# Sheet1.net
KiCad netlist of a schematic drawn in Altium Designer
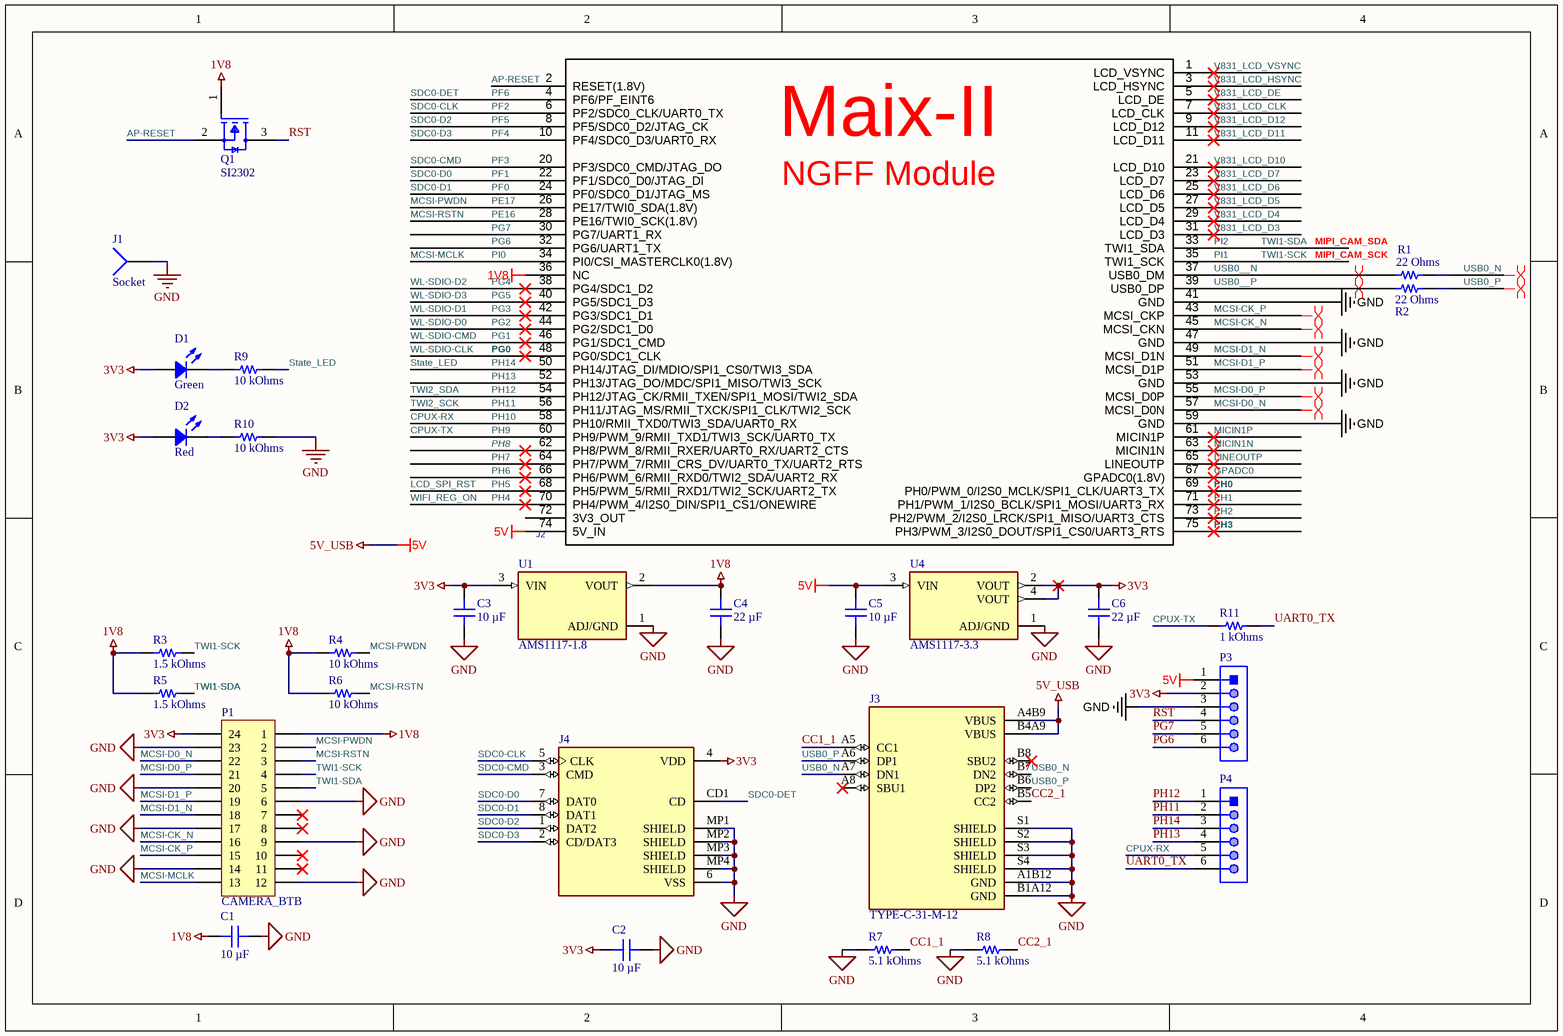
[diagram p0: Sheet1.SchDoc]

(export (version "E")
  (design (tool "Eeschema 10.0.6"))
  (components
    (comp (ref "C1")
      (value "10 µF")
      (footprint "CAP 0402_1005")
      (description "CAP CER 10UF 2.5V X5R 0402")
      (fields
        (field (name "PART NUMBER") "GRM155R60E106ME16D")
        (field (name "MANUFACTURER") "Murata Electronics")
      )
      (libsource (lib "Celestial Altium Library - altium_library") (part "Capacitor"))
    )
    (comp (ref "C2")
      (value "10 µF")
      (footprint "CAP 0402_1005")
      (description "CAP CER 10UF 2.5V X5R 0402")
      (fields
        (field (name "PART NUMBER") "GRM155R60E106ME16D")
        (field (name "MANUFACTURER") "Murata Electronics")
      )
      (libsource (lib "Celestial Altium Library - altium_library") (part "Capacitor"))
    )
    (comp (ref "C3")
      (value "10 µF")
      (footprint "CAP 0402_1005")
      (description "CAP CER 10UF 2.5V X5R 0402")
      (fields
        (field (name "PART NUMBER") "GRM155R60E106ME16D")
        (field (name "MANUFACTURER") "Murata Electronics")
      )
      (libsource (lib "Celestial Altium Library - altium_library") (part "Capacitor"))
    )
    (comp (ref "C4")
      (value "22 µF")
      (footprint "CAP_TAN_A1206")
      (description "CAP CER 10UF 2.5V X5R 0402")
      (fields
        (field (name "PART NUMBER") "GRM155R60E106ME16D")
        (field (name "MANUFACTURER") "Murata Electronics")
      )
      (libsource (lib "Celestial Altium Library - altium_library") (part "Capacitor"))
    )
    (comp (ref "C5")
      (value "10 µF")
      (footprint "CAP 0402_1005")
      (description "CAP CER 10UF 2.5V X5R 0402")
      (fields
        (field (name "PART NUMBER") "GRM155R60E106ME16D")
        (field (name "MANUFACTURER") "Murata Electronics")
      )
      (libsource (lib "Celestial Altium Library - altium_library") (part "Capacitor"))
    )
    (comp (ref "C6")
      (value "22 µF")
      (footprint "CAP_TAN_A1206")
      (description "CAP CER 10UF 2.5V X5R 0402")
      (fields
        (field (name "PART NUMBER") "GRM155R60E106ME16D")
        (field (name "MANUFACTURER") "Murata Electronics")
      )
      (libsource (lib "Celestial Altium Library - altium_library") (part "Capacitor"))
    )
    (comp (ref "D1")
      (value "Green")
      (footprint "LED_0603_GREEN")
      (description "LED GREEN CLEAR 2SMD")
      (fields
        (field (name "PART NUMBER") "EAST10052GA0")
        (field (name "MANUFACTURER") "Everlight Electronics Co Ltd")
      )
      (libsource (lib "Celestial Altium Library - altium_library") (part "LED"))
    )
    (comp (ref "D2")
      (value "Red")
      (footprint "LED_0603_RED")
      (description "0402 LED RED, CLEAR LENS, 330MCD")
      (fields (field (name "PART NUMBER") "QBLP595-R-2897") (field (name "MANUFACTURER") "QT Brightek (QTB)"))
      (libsource (lib "Celestial Altium Library - altium_library") (part "LED"))
    )
    (comp (ref "J1")
      (value "Socket")
      (footprint "M.2 SMT-FEMALE - FULL")
      (fields (field (name "PUBLISHER") "Altium Limited"))
      (libsource (lib "Miscellaneous Connectors") (part "Socket"))
    )
    (comp (ref "J2")
      (value "NGFF-67P_B-KEY座子 4.2H高")
      (footprint "M2-67P0R50_B_FEMALE")
      (libsource (lib "V831_Dock_3060") (part "NGFF-67P_B-MALE"))
    )
    (comp (ref "J3")
      (value "TYPE-C-31-M-12")
      (footprint "HRO_TYPE-C-31-M-12")
      (description "USB Connectors 24 Receptacle 1 8.94*7.3mm RoHS")
      (fields (field (name "MF") "{'manufacturer': u'HRO Electronics Co., Ltd.'}"))
      (libsource (lib "SnapEDA_Library") (part "TYPE-C-31-M-12"))
    )
    (comp (ref "J4")
      (value "TF-01A")
      (footprint "TF-01A")
      (fields (field (name "MF") "{'manufacturer': u'HRO Electronics Co., Ltd.'}"))
      (libsource (lib "SnapEDA_Library") (part "TF-01A"))
    )
    (comp (ref "P1")
      (value "CAMERA_BTB")
      (footprint "F_24PIN")
      (description "Header, 12-Pin, Dual row")
      (fields (field (name "PUBLISHER") "Altium Limited"))
      (libsource (lib "maix_2") (part "Header 12X2A"))
    )
    (comp (ref "P3")
      (value "61300611121")
      (footprint "61300611121")
      (description "THT Vertical Pin Header WR-PHD, Pitch 2.54 mm, Single Row, 6 pins")
      (fields (field (name "MANUFACTURER") "Wurth Elektronik") (field (name "PUBLISHER") "WurthElektronik"))
      (libsource (lib "Altium Content Vault") (part "WE-CN-1P-M-R6"))
    )
    (comp (ref "P4")
      (value "61300611121")
      (footprint "61300611121")
      (description "THT Vertical Pin Header WR-PHD, Pitch 2.54 mm, Single Row, 6 pins")
      (fields (field (name "MANUFACTURER") "Wurth Elektronik") (field (name "PUBLISHER") "WurthElektronik"))
      (libsource (lib "Altium Content Vault") (part "WE-CN-1P-M-R6"))
    )
    (comp (ref "Q1")
      (value "SI2302")
      (footprint "FP-S-03946-IPC_B")
      (description "MOSFET N-CH 20V 2.9A SOT23-3")
      (libsource (lib "Altium Content Vault") (part "0a9ea7c96deaaede766a5b531c28de0"))
    )
    (comp (ref "R1")
      (value "22 Ohms")
      (footprint "RES 0402_1005")
      (description "RES 22 OHM 1% 1/8W 0402")
      (fields (field (name "PART NUMBER") "SR0402FR-7W22RL") (field (name "MANUFACTURER") "Yageo"))
      (libsource (lib "Celestial Altium Library - altium_library") (part "Resistor"))
    )
    (comp (ref "R2")
      (value "22 Ohms")
      (footprint "RES 0402_1005")
      (description "RES 22 OHM 1% 1/8W 0402")
      (fields (field (name "PART NUMBER") "SR0402FR-7W22RL") (field (name "MANUFACTURER") "Yageo"))
      (libsource (lib "Celestial Altium Library - altium_library") (part "Resistor"))
    )
    (comp (ref "R3")
      (value "1.5 kOhms")
      (footprint "RES 0402_1005")
      (description "PTN0402 10PPM 1.5K 0.1% S T1 E1")
      (fields
        (field (name "PART NUMBER") "PTN0402Y1501BST1")
        (field (name "MANUFACTURER") "Vishay Dale Thin Film")
      )
      (libsource (lib "Celestial Altium Library - altium_library") (part "Resistor"))
    )
    (comp (ref "R4")
      (value "10 kOhms")
      (footprint "RES 0402_1005")
      (description "P2TC0402 2PPM/C 10K 0,01% N TA")
      (fields
        (field (name "PART NUMBER") "P2TC0402D1002LNTA")
        (field (name "MANUFACTURER") "Vishay Sfernice")
      )
      (libsource (lib "Celestial Altium Library - altium_library") (part "Resistor"))
    )
    (comp (ref "R5")
      (value "1.5 kOhms")
      (footprint "RES 0402_1005")
      (description "PTN0402 10PPM 1.5K 0.1% S T1 E1")
      (fields
        (field (name "PART NUMBER") "PTN0402Y1501BST1")
        (field (name "MANUFACTURER") "Vishay Dale Thin Film")
      )
      (libsource (lib "Celestial Altium Library - altium_library") (part "Resistor"))
    )
    (comp (ref "R6")
      (value "10 kOhms")
      (footprint "RES 0402_1005")
      (description "P2TC0402 2PPM/C 10K 0,01% N TA")
      (fields
        (field (name "PART NUMBER") "P2TC0402D1002LNTA")
        (field (name "MANUFACTURER") "Vishay Sfernice")
      )
      (libsource (lib "Celestial Altium Library - altium_library") (part "Resistor"))
    )
    (comp (ref "R7")
      (value "5.1 kOhms")
      (footprint "RES 0402_1005")
      (description "RES 5.1K OHM 0.1% 1/16W 0402")
      (fields
        (field (name "PART NUMBER") "RN73R1ETTP5101B25")
        (field (name "MANUFACTURER") "KOA Speer Electronics, Inc.")
      )
      (libsource (lib "Celestial Altium Library - altium_library") (part "Resistor"))
    )
    (comp (ref "R8")
      (value "5.1 kOhms")
      (footprint "RES 0402_1005")
      (description "RES 5.1K OHM 0.1% 1/16W 0402")
      (fields
        (field (name "PART NUMBER") "RN73R1ETTP5101B25")
        (field (name "MANUFACTURER") "KOA Speer Electronics, Inc.")
      )
      (libsource (lib "Celestial Altium Library - altium_library") (part "Resistor"))
    )
    (comp (ref "R9")
      (value "10 kOhms")
      (footprint "RES 0402_1005")
      (description "RES 10K OHM 0.1% 1/10W 0402")
      (fields
        (field (name "PART NUMBER") "RP73PF1E10KBTD")
        (field (name "MANUFACTURER") "TE Connectivity Passive Product")
      )
      (libsource (lib "Celestial Altium Library - altium_library") (part "Resistor"))
    )
    (comp (ref "R10")
      (value "10 kOhms")
      (footprint "RES 0402_1005")
      (description "RES 10K OHM 0.1% 1/10W 0402")
      (fields
        (field (name "PART NUMBER") "RP73PF1E10KBTD")
        (field (name "MANUFACTURER") "TE Connectivity Passive Product")
      )
      (libsource (lib "Celestial Altium Library - altium_library") (part "Resistor"))
    )
    (comp (ref "R11")
      (value "1 kOhms")
      (footprint "RES 0402_1005")
      (description "RES 1K OHM 0.01% 1/16W 0402")
      (fields
        (field (name "PART NUMBER") "RNCF0402TKY1K00")
        (field (name "MANUFACTURER") "Stackpole Electronics Inc")
      )
      (libsource (lib "Celestial Altium Library - altium_library") (part "Resistor"))
    )
    (comp (ref "U1")
      (value "AMS1117-1.8")
      (footprint "SOT89-3")
      (description "Sot223/Pkg 1-Amp 5-Volt Low Drop Out Voltage Regulatator")
      (fields
        (field (name "MP") "AMS1117")
        (field (name "MF") "{'manufacturer': u'Advanced Monolithic Systems'}")
      )
      (libsource (lib "maix_2") (part "AMS1117"))
    )
    (comp (ref "U4")
      (value "AMS1117-3.3")
      (footprint "SOT229P700X180-4N")
      (description "Sot223/Pkg 1-Amp 5-Volt Low Drop Out Voltage Regulatator")
      (fields
        (field (name "MP") "AMS1117")
        (field (name "MF") "{'manufacturer': u'Advanced Monolithic Systems'}")
      )
      (libsource (lib "") (part "AMS1117_1"))
    )
  )
  (nets
    (net (code "1") (name "/AP-RESET") (class "Default")
      (node (ref "J2") (pin "2") (pinfunction "RESET(1.8V)_2") (pintype "passive"))
      (node (ref "Q1") (pin "2") (pinfunction "S_2") (pintype "passive"))
    )
    (net (code "2") (name "/CC1_1") (class "Default")
      (node (ref "J3") (pin "A5") (pinfunction "CC1_A5") (pintype "bidirectional"))
      (node (ref "R7") (pin "2") (pinfunction "2_2") (pintype "passive"))
    )
    (net (code "3") (name "/CC2_1") (class "Default")
      (node (ref "J3") (pin "B5") (pinfunction "CC2_B5") (pintype "bidirectional"))
      (node (ref "R8") (pin "2") (pinfunction "2_2") (pintype "passive"))
    )
    (net (code "4") (name "/CPUX-RX") (class "Default")
      (node (ref "J2") (pin "58") (pinfunction "PH10/RMII_TXD0/TWI3_SDA/UART0_RX_58") (pintype "passive"))
      (node (ref "P4") (pin "5") (pinfunction "5_5") (pintype "passive"))
    )
    (net (code "5") (name "/CPUX-TX") (class "Default")
      (node (ref "J2") (pin "60") (pinfunction "PH9/PWM_9/RMII_TXD1/TWI3_SCK/UART0_TX_60") (pintype "passive"))
      (node (ref "R11") (pin "1") (pinfunction "1_1") (pintype "passive"))
    )
    (net (code "6") (name "/GPADC0") (class "Default")
      (node (ref "J2") (pin "67") (pinfunction "GPADC0(1.8V)_67") (pintype "passive+no_connect"))
    )
    (net (code "7") (name "/LCD_SPI_RST") (class "Default")
      (node (ref "J2") (pin "68") (pinfunction "PH5/PWM_5/RMII_RXD1/TWI2_SCK/UART2_TX_68") (pintype "passive+no_connect"))
    )
    (net (code "8") (name "/LINEOUTP") (class "Default")
      (node (ref "J2") (pin "65") (pinfunction "LINEOUTP_65") (pintype "passive+no_connect"))
    )
    (net (code "9") (name "/MCSI-CK_N") (class "Default")
      (node (ref "J2") (pin "45") (pinfunction "MCSI_CKN_45") (pintype "passive"))
      (node (ref "P1") (pin "16") (pinfunction "16_16") (pintype "passive"))
    )
    (net (code "10") (name "/MCSI-CK_P") (class "Default")
      (node (ref "J2") (pin "43") (pinfunction "MCSI_CKP_43") (pintype "passive"))
      (node (ref "P1") (pin "15") (pinfunction "15_15") (pintype "passive"))
    )
    (net (code "11") (name "/MCSI-D0_N") (class "Default")
      (node (ref "J2") (pin "57") (pinfunction "MCSI_D0N_57") (pintype "passive"))
      (node (ref "P1") (pin "22") (pinfunction "22_22") (pintype "passive"))
    )
    (net (code "12") (name "/MCSI-D0_P") (class "Default")
      (node (ref "J2") (pin "55") (pinfunction "MCSI_D0P_55") (pintype "passive"))
      (node (ref "P1") (pin "21") (pinfunction "21_21") (pintype "passive"))
    )
    (net (code "13") (name "/MCSI-D1_N") (class "Default")
      (node (ref "J2") (pin "49") (pinfunction "MCSI_D1N_49") (pintype "passive"))
      (node (ref "P1") (pin "18") (pinfunction "18_18") (pintype "passive"))
    )
    (net (code "14") (name "/MCSI-D1_P") (class "Default")
      (node (ref "J2") (pin "51") (pinfunction "MCSI_D1P_51") (pintype "passive"))
      (node (ref "P1") (pin "19") (pinfunction "19_19") (pintype "passive"))
    )
    (net (code "15") (name "/MCSI-MCLK") (class "Default")
      (node (ref "J2") (pin "34") (pinfunction "PI0/CSI_MASTERCLK0(1.8V)_34") (pintype "passive"))
      (node (ref "P1") (pin "13") (pinfunction "13_13") (pintype "passive"))
    )
    (net (code "16") (name "/MCSI-PWDN") (class "Default")
      (node (ref "J2") (pin "26") (pinfunction "PE17/TWI0_SDA(1.8V)_26") (pintype "passive"))
      (node (ref "P1") (pin "2") (pinfunction "2_2") (pintype "passive"))
      (node (ref "R4") (pin "2") (pinfunction "2_2") (pintype "passive"))
    )
    (net (code "17") (name "/MCSI-RSTN") (class "Default")
      (node (ref "J2") (pin "28") (pinfunction "PE16/TWI0_SCK(1.8V)_28") (pintype "passive"))
      (node (ref "P1") (pin "3") (pinfunction "3_3") (pintype "passive"))
      (node (ref "R6") (pin "2") (pinfunction "2_2") (pintype "passive"))
    )
    (net (code "18") (name "/MICIN1N") (class "Default")
      (node (ref "J2") (pin "63") (pinfunction "MICIN1N_63") (pintype "passive+no_connect"))
    )
    (net (code "19") (name "/MICIN1P") (class "Default")
      (node (ref "J2") (pin "61") (pinfunction "MICIN1P_61") (pintype "passive+no_connect"))
    )
    (net (code "20") (name "/PF0") (class "Default")
      (node (ref "J2") (pin "24") (pinfunction "PF0/SDC0_D1/JTAG_MS_24") (pintype "passive"))
      (node (ref "J4") (pin "8") (pinfunction "DAT1_8") (pintype "bidirectional"))
    )
    (net (code "21") (name "/PF1") (class "Default")
      (node (ref "J2") (pin "22") (pinfunction "PF1/SDC0_D0/JTAG_DI_22") (pintype "passive"))
      (node (ref "J4") (pin "7") (pinfunction "DAT0_7") (pintype "bidirectional"))
    )
    (net (code "22") (name "/PF2") (class "Default")
      (node (ref "J2") (pin "6") (pinfunction "PF2/SDC0_CLK/UART0_TX_6") (pintype "passive"))
      (node (ref "J4") (pin "5") (pinfunction "CLK_5") (pintype "bidirectional"))
    )
    (net (code "23") (name "/PF3") (class "Default")
      (node (ref "J2") (pin "20") (pinfunction "PF3/SDC0_CMD/JTAG_DO_20") (pintype "passive"))
      (node (ref "J4") (pin "3") (pinfunction "CMD_3") (pintype "bidirectional"))
    )
    (net (code "24") (name "/PF4") (class "Default")
      (node (ref "J2") (pin "10") (pinfunction "PF4/SDC0_D3/UART0_RX_10") (pintype "passive"))
      (node (ref "J4") (pin "2") (pinfunction "CD/DAT3_2") (pintype "bidirectional"))
    )
    (net (code "25") (name "/PF5") (class "Default")
      (node (ref "J2") (pin "8") (pinfunction "PF5/SDC0_D2/JTAG_CK_8") (pintype "passive"))
      (node (ref "J4") (pin "1") (pinfunction "DAT2_1") (pintype "bidirectional"))
    )
    (net (code "26") (name "/PF6") (class "Default")
      (node (ref "J2") (pin "4") (pinfunction "PF6/PF_EINT6_4") (pintype "passive"))
      (node (ref "J4") (pin "CD1") (pinfunction "CD_CD1") (pintype "passive"))
    )
    (net (code "27") (name "/PG0") (class "Default")
      (node (ref "J2") (pin "48") (pinfunction "PG0/SDC1_CLK_48") (pintype "passive+no_connect"))
    )
    (net (code "28") (name "/PG1") (class "Default")
      (node (ref "J2") (pin "46") (pinfunction "PG1/SDC1_CMD_46") (pintype "passive+no_connect"))
    )
    (net (code "29") (name "/PG2") (class "Default")
      (node (ref "J2") (pin "44") (pinfunction "PG2/SDC1_D0_44") (pintype "passive+no_connect"))
    )
    (net (code "30") (name "/PG3") (class "Default")
      (node (ref "J2") (pin "42") (pinfunction "PG3/SDC1_D1_42") (pintype "passive+no_connect"))
    )
    (net (code "31") (name "/PG4") (class "Default")
      (node (ref "J2") (pin "38") (pinfunction "PG4/SDC1_D2_38") (pintype "passive+no_connect"))
    )
    (net (code "32") (name "/PG5") (class "Default")
      (node (ref "J2") (pin "40") (pinfunction "PG5/SDC1_D3_40") (pintype "passive+no_connect"))
    )
    (net (code "33") (name "/PG6") (class "Default")
      (node (ref "J2") (pin "32") (pinfunction "PG6/UART1_TX_32") (pintype "passive"))
      (node (ref "P3") (pin "6") (pinfunction "6_6") (pintype "passive"))
    )
    (net (code "34") (name "/PG7") (class "Default")
      (node (ref "J2") (pin "30") (pinfunction "PG7/UART1_RX_30") (pintype "passive"))
      (node (ref "P3") (pin "5") (pinfunction "5_5") (pintype "passive"))
    )
    (net (code "35") (name "/PH0") (class "Default")
      (node (ref "J2") (pin "69") (pinfunction "PH0/PWM_0/I2S0_MCLK/SPI1_CLK/UART3_TX_69") (pintype "passive+no_connect"))
    )
    (net (code "36") (name "/PH1") (class "Default")
      (node (ref "J2") (pin "71") (pinfunction "PH1/PWM_1/I2S0_BCLK/SPI1_MOSI/UART3_RX_71") (pintype "passive+no_connect"))
    )
    (net (code "37") (name "/PH2") (class "Default")
      (node (ref "J2") (pin "73") (pinfunction "PH2/PWM_2/I2S0_LRCK/SPI1_MISO/UART3_CTS_73") (pintype "passive+no_connect"))
    )
    (net (code "38") (name "/PH3") (class "Default")
      (node (ref "J2") (pin "75") (pinfunction "PH3/PWM_3/I2S0_DOUT/SPI1_CS0/UART3_RTS_75") (pintype "passive+no_connect"))
    )
    (net (code "39") (name "/PH4") (class "Default")
      (node (ref "J2") (pin "70") (pinfunction "PH4/PWM_4/I2S0_DIN/SPI1_CS1/ONEWIRE_70") (pintype "passive+no_connect"))
    )
    (net (code "40") (name "/PH6") (class "Default")
      (node (ref "J2") (pin "66") (pinfunction "PH6/PWM_6/RMII_RXD0/TWI2_SDA/UART2_RX_66") (pintype "passive+no_connect"))
    )
    (net (code "41") (name "/PH7") (class "Default")
      (node (ref "J2") (pin "64") (pinfunction "PH7/PWM_7/RMII_CRS_DV/UART0_TX/UART2_RTS_64") (pintype "passive+no_connect"))
    )
    (net (code "42") (name "/PH8") (class "Default")
      (node (ref "J2") (pin "62") (pinfunction "PH8/PWM_8/RMII_RXER/UART0_RX/UART2_CTS_62") (pintype "passive+no_connect"))
    )
    (net (code "43") (name "/PH11") (class "Default")
      (node (ref "J2") (pin "56") (pinfunction "PH11/JTAG_MS/RMII_TXCK/SPI1_CLK/TWI2_SCK_56") (pintype "passive"))
      (node (ref "P4") (pin "2") (pinfunction "2_2") (pintype "passive"))
    )
    (net (code "44") (name "/PH12") (class "Default")
      (node (ref "J2") (pin "54") (pinfunction "PH12/JTAG_CK/RMII_TXEN/SPI1_MOSI/TWI2_SDA_54") (pintype "passive"))
      (node (ref "P4") (pin "1") (pinfunction "1_1") (pintype "passive"))
    )
    (net (code "45") (name "/PH13") (class "Default")
      (node (ref "J2") (pin "52") (pinfunction "PH13/JTAG_DO/MDC/SPI1_MISO/TWI3_SCK_52") (pintype "passive"))
      (node (ref "P4") (pin "4") (pinfunction "4_4") (pintype "passive"))
    )
    (net (code "46") (name "/PH14") (class "Default")
      (node (ref "J2") (pin "50") (pinfunction "PH14/JTAG_DI/MDIO/SPI1_CS0/TWI3_SDA_50") (pintype "passive"))
      (node (ref "P4") (pin "3") (pinfunction "3_3") (pintype "passive"))
      (node (ref "R9") (pin "2") (pinfunction "2_2") (pintype "passive"))
    )
    (net (code "47") (name "/PI1") (class "Default")
      (node (ref "J2") (pin "35") (pinfunction "TWI1_SCK_35") (pintype "passive"))
      (node (ref "P1") (pin "4") (pinfunction "4_4") (pintype "passive"))
      (node (ref "R3") (pin "2") (pinfunction "2_2") (pintype "passive"))
    )
    (net (code "48") (name "/PI2") (class "Default")
      (node (ref "J2") (pin "33") (pinfunction "TWI1_SDA_33") (pintype "passive"))
      (node (ref "P1") (pin "5") (pinfunction "5_5") (pintype "passive"))
      (node (ref "R5") (pin "2") (pinfunction "2_2") (pintype "passive"))
    )
    (net (code "49") (name "/RST") (class "Default")
      (node (ref "P3") (pin "4") (pinfunction "4_4") (pintype "passive"))
      (node (ref "Q1") (pin "3") (pinfunction "D_3") (pintype "passive"))
    )
    (net (code "50") (name "/UART0_TX") (class "Default")
      (node (ref "P4") (pin "6") (pinfunction "6_6") (pintype "passive"))
      (node (ref "R11") (pin "2") (pinfunction "2_2") (pintype "passive"))
    )
    (net (code "51") (name "/USB0_N") (class "Default")
      (node (ref "J3") (pin "A7") (pinfunction "DN1_A7") (pintype "bidirectional"))
      (node (ref "J3") (pin "B7") (pinfunction "DN2_B7") (pintype "bidirectional"))
      (node (ref "R1") (pin "2") (pinfunction "2_2") (pintype "passive"))
    )
    (net (code "52") (name "/USB0_P") (class "Default")
      (node (ref "J3") (pin "A6") (pinfunction "DP1_A6") (pintype "bidirectional"))
      (node (ref "J3") (pin "B6") (pinfunction "DP2_B6") (pintype "bidirectional"))
      (node (ref "R2") (pin "2") (pinfunction "2_2") (pintype "passive"))
    )
    (net (code "53") (name "/USB0__N") (class "Default")
      (node (ref "J2") (pin "37") (pinfunction "USB0_DM_37") (pintype "passive"))
      (node (ref "R1") (pin "1") (pinfunction "1_1") (pintype "passive"))
    )
    (net (code "54") (name "/USB0__P") (class "Default")
      (node (ref "J2") (pin "39") (pinfunction "USB0_DP_39") (pintype "passive"))
      (node (ref "R2") (pin "1") (pinfunction "1_1") (pintype "passive"))
    )
    (net (code "55") (name "/V831_LCD_CLK") (class "Default")
      (node (ref "J2") (pin "7") (pinfunction "LCD_CLK_7") (pintype "passive+no_connect"))
    )
    (net (code "56") (name "/V831_LCD_D3") (class "Default")
      (node (ref "J2") (pin "31") (pinfunction "LCD_D3_31") (pintype "passive+no_connect"))
    )
    (net (code "57") (name "/V831_LCD_D4") (class "Default")
      (node (ref "J2") (pin "29") (pinfunction "LCD_D4_29") (pintype "passive+no_connect"))
    )
    (net (code "58") (name "/V831_LCD_D5") (class "Default")
      (node (ref "J2") (pin "27") (pinfunction "LCD_D5_27") (pintype "passive+no_connect"))
    )
    (net (code "59") (name "/V831_LCD_D6") (class "Default")
      (node (ref "J2") (pin "25") (pinfunction "LCD_D6_25") (pintype "passive+no_connect"))
    )
    (net (code "60") (name "/V831_LCD_D7") (class "Default")
      (node (ref "J2") (pin "23") (pinfunction "LCD_D7_23") (pintype "passive+no_connect"))
    )
    (net (code "61") (name "/V831_LCD_D10") (class "Default")
      (node (ref "J2") (pin "21") (pinfunction "LCD_D10_21") (pintype "passive+no_connect"))
    )
    (net (code "62") (name "/V831_LCD_D11") (class "Default")
      (node (ref "J2") (pin "11") (pinfunction "LCD_D11_11") (pintype "passive+no_connect"))
    )
    (net (code "63") (name "/V831_LCD_D12") (class "Default")
      (node (ref "J2") (pin "9") (pinfunction "LCD_D12_9") (pintype "passive+no_connect"))
    )
    (net (code "64") (name "/V831_LCD_DE") (class "Default")
      (node (ref "J2") (pin "5") (pinfunction "LCD_DE_5") (pintype "passive+no_connect"))
    )
    (net (code "65") (name "/V831_LCD_HSYNC") (class "Default")
      (node (ref "J2") (pin "3") (pinfunction "LCD_HSYNC_3") (pintype "passive+no_connect"))
    )
    (net (code "66") (name "/V831_LCD_VSYNC") (class "Default")
      (node (ref "J2") (pin "1") (pinfunction "LCD_VSYNC_1") (pintype "passive+no_connect"))
    )
    (net (code "67") (name "1V8") (class "Default")
      (node (ref "C1") (pin "1") (pinfunction "1_1") (pintype "passive"))
      (node (ref "C4") (pin "1") (pinfunction "1_1") (pintype "passive"))
      (node (ref "J2") (pin "36") (pinfunction "NC_36") (pintype "passive"))
      (node (ref "P1") (pin "1") (pinfunction "1_1") (pintype "passive"))
      (node (ref "Q1") (pin "1") (pinfunction "G_1") (pintype "passive"))
      (node (ref "R3") (pin "1") (pinfunction "1_1") (pintype "passive"))
      (node (ref "R4") (pin "1") (pinfunction "1_1") (pintype "passive"))
      (node (ref "R5") (pin "1") (pinfunction "1_1") (pintype "passive"))
      (node (ref "R6") (pin "1") (pinfunction "1_1") (pintype "passive"))
      (node (ref "U1") (pin "2") (pinfunction "VOUT_2") (pintype "output"))
    )
    (net (code "68") (name "3V3") (class "Default")
      (node (ref "C2") (pin "1") (pinfunction "1_1") (pintype "passive"))
      (node (ref "C3") (pin "1") (pinfunction "1_1") (pintype "passive"))
      (node (ref "C6") (pin "1") (pinfunction "1_1") (pintype "passive"))
      (node (ref "D1") (pin "1") (pinfunction "1_1") (pintype "passive"))
      (node (ref "D2") (pin "1") (pinfunction "1_1") (pintype "passive"))
      (node (ref "J4") (pin "4") (pinfunction "VDD_4") (pintype "power_in"))
      (node (ref "P1") (pin "24") (pinfunction "24_24") (pintype "passive"))
      (node (ref "P3") (pin "2") (pinfunction "2_2") (pintype "passive"))
      (node (ref "U1") (pin "3") (pinfunction "VIN_3") (pintype "input"))
      (node (ref "U4") (pin "2") (pinfunction "VOUT_2") (pintype "output"))
      (node (ref "U4") (pin "4") (pinfunction "VOUT_4") (pintype "output"))
    )
    (net (code "69") (name "5V") (class "Default")
      (node (ref "C5") (pin "1") (pinfunction "1_1") (pintype "passive"))
      (node (ref "J2") (pin "74") (pinfunction "5V_IN_74") (pintype "passive"))
      (node (ref "J3") (pin "A4B9") (pinfunction "VBUS_A4B9") (pintype "power_in"))
      (node (ref "J3") (pin "B4A9") (pinfunction "VBUS_B4A9") (pintype "power_in"))
      (node (ref "P3") (pin "1") (pinfunction "1_1") (pintype "passive"))
      (node (ref "U4") (pin "3") (pinfunction "VIN_3") (pintype "input"))
    )
    (net (code "70") (name "GND") (class "Default")
      (node (ref "C1") (pin "2") (pinfunction "2_2") (pintype "passive"))
      (node (ref "C2") (pin "2") (pinfunction "2_2") (pintype "passive"))
      (node (ref "C3") (pin "2") (pinfunction "2_2") (pintype "passive"))
      (node (ref "C4") (pin "2") (pinfunction "2_2") (pintype "passive"))
      (node (ref "C5") (pin "2") (pinfunction "2_2") (pintype "passive"))
      (node (ref "C6") (pin "2") (pinfunction "2_2") (pintype "passive"))
      (node (ref "J1") (pin "1") (pinfunction "1_1") (pintype "passive"))
      (node (ref "J2") (pin "41") (pinfunction "GND_41") (pintype "passive"))
      (node (ref "J2") (pin "47") (pinfunction "GND_47") (pintype "passive"))
      (node (ref "J2") (pin "53") (pinfunction "GND_53") (pintype "passive"))
      (node (ref "J2") (pin "59") (pinfunction "GND_59") (pintype "passive"))
      (node (ref "J3") (pin "A1B12") (pinfunction "GND_A1B12") (pintype "power_in"))
      (node (ref "J3") (pin "B1A12") (pinfunction "GND_B1A12") (pintype "power_in"))
      (node (ref "J3") (pin "S1") (pinfunction "SHIELD_S1") (pintype "passive"))
      (node (ref "J3") (pin "S2") (pinfunction "SHIELD_S2") (pintype "passive"))
      (node (ref "J3") (pin "S3") (pinfunction "SHIELD_S3") (pintype "passive"))
      (node (ref "J3") (pin "S4") (pinfunction "SHIELD_S4") (pintype "passive"))
      (node (ref "J4") (pin "6") (pinfunction "VSS_6") (pintype "power_in"))
      (node (ref "J4") (pin "MP1") (pinfunction "SHIELD_MP1") (pintype "power_in"))
      (node (ref "J4") (pin "MP2") (pinfunction "SHIELD_MP2") (pintype "power_in"))
      (node (ref "J4") (pin "MP3") (pinfunction "SHIELD_MP3") (pintype "power_in"))
      (node (ref "J4") (pin "MP4") (pinfunction "SHIELD_MP4") (pintype "power_in"))
      (node (ref "P1") (pin "12") (pinfunction "12_12") (pintype "passive"))
      (node (ref "P1") (pin "14") (pinfunction "14_14") (pintype "passive"))
      (node (ref "P1") (pin "17") (pinfunction "17_17") (pintype "passive"))
      (node (ref "P1") (pin "20") (pinfunction "20_20") (pintype "passive"))
      (node (ref "P1") (pin "23") (pinfunction "23_23") (pintype "passive"))
      (node (ref "P1") (pin "6") (pinfunction "6_6") (pintype "passive"))
      (node (ref "P1") (pin "9") (pinfunction "9_9") (pintype "passive"))
      (node (ref "P3") (pin "3") (pinfunction "3_3") (pintype "passive"))
      (node (ref "R10") (pin "2") (pinfunction "2_2") (pintype "passive"))
      (node (ref "R7") (pin "1") (pinfunction "1_1") (pintype "passive"))
      (node (ref "R8") (pin "1") (pinfunction "1_1") (pintype "passive"))
      (node (ref "U1") (pin "1") (pinfunction "ADJ/GND_1") (pintype "power_in"))
      (node (ref "U4") (pin "1") (pinfunction "ADJ/GND_1") (pintype "power_in"))
    )
    (net (code "71") (name "Net-(D1-Pad2)") (class "Default")
      (node (ref "D1") (pin "2") (pinfunction "2_2") (pintype "passive"))
      (node (ref "R9") (pin "1") (pinfunction "1_1") (pintype "passive"))
    )
    (net (code "72") (name "Net-(D2-Pad2)") (class "Default")
      (node (ref "D2") (pin "2") (pinfunction "2_2") (pintype "passive"))
      (node (ref "R10") (pin "1") (pinfunction "1_1") (pintype "passive"))
    )
    (net (code "73") (name "unconnected-(J2-3V3_OUT-Pad72)") (class "Default")
      (node (ref "J2") (pin "72") (pinfunction "3V3_OUT_72") (pintype "passive"))
    )
    (net (code "74") (name "unconnected-(J3-SBU1-PadA8)") (class "Default")
      (node (ref "J3") (pin "A8") (pinfunction "SBU1_A8") (pintype "bidirectional+no_connect"))
    )
    (net (code "75") (name "unconnected-(J3-SBU2-PadB8)") (class "Default")
      (node (ref "J3") (pin "B8") (pinfunction "SBU2_B8") (pintype "bidirectional+no_connect"))
    )
    (net (code "76") (name "unconnected-(P1-Pad7)") (class "Default")
      (node (ref "P1") (pin "7") (pinfunction "7_7") (pintype "passive+no_connect"))
    )
    (net (code "77") (name "unconnected-(P1-Pad8)") (class "Default")
      (node (ref "P1") (pin "8") (pinfunction "8_8") (pintype "passive+no_connect"))
    )
    (net (code "78") (name "unconnected-(P1-Pad10)") (class "Default")
      (node (ref "P1") (pin "10") (pinfunction "10_10") (pintype "passive+no_connect"))
    )
    (net (code "79") (name "unconnected-(P1-Pad11)") (class "Default")
      (node (ref "P1") (pin "11") (pinfunction "11_11") (pintype "passive+no_connect"))
    )
  )
)
